# x-IMU3-SA-IMU.net
KiCad netlist of a schematic drawn in Altium Designer
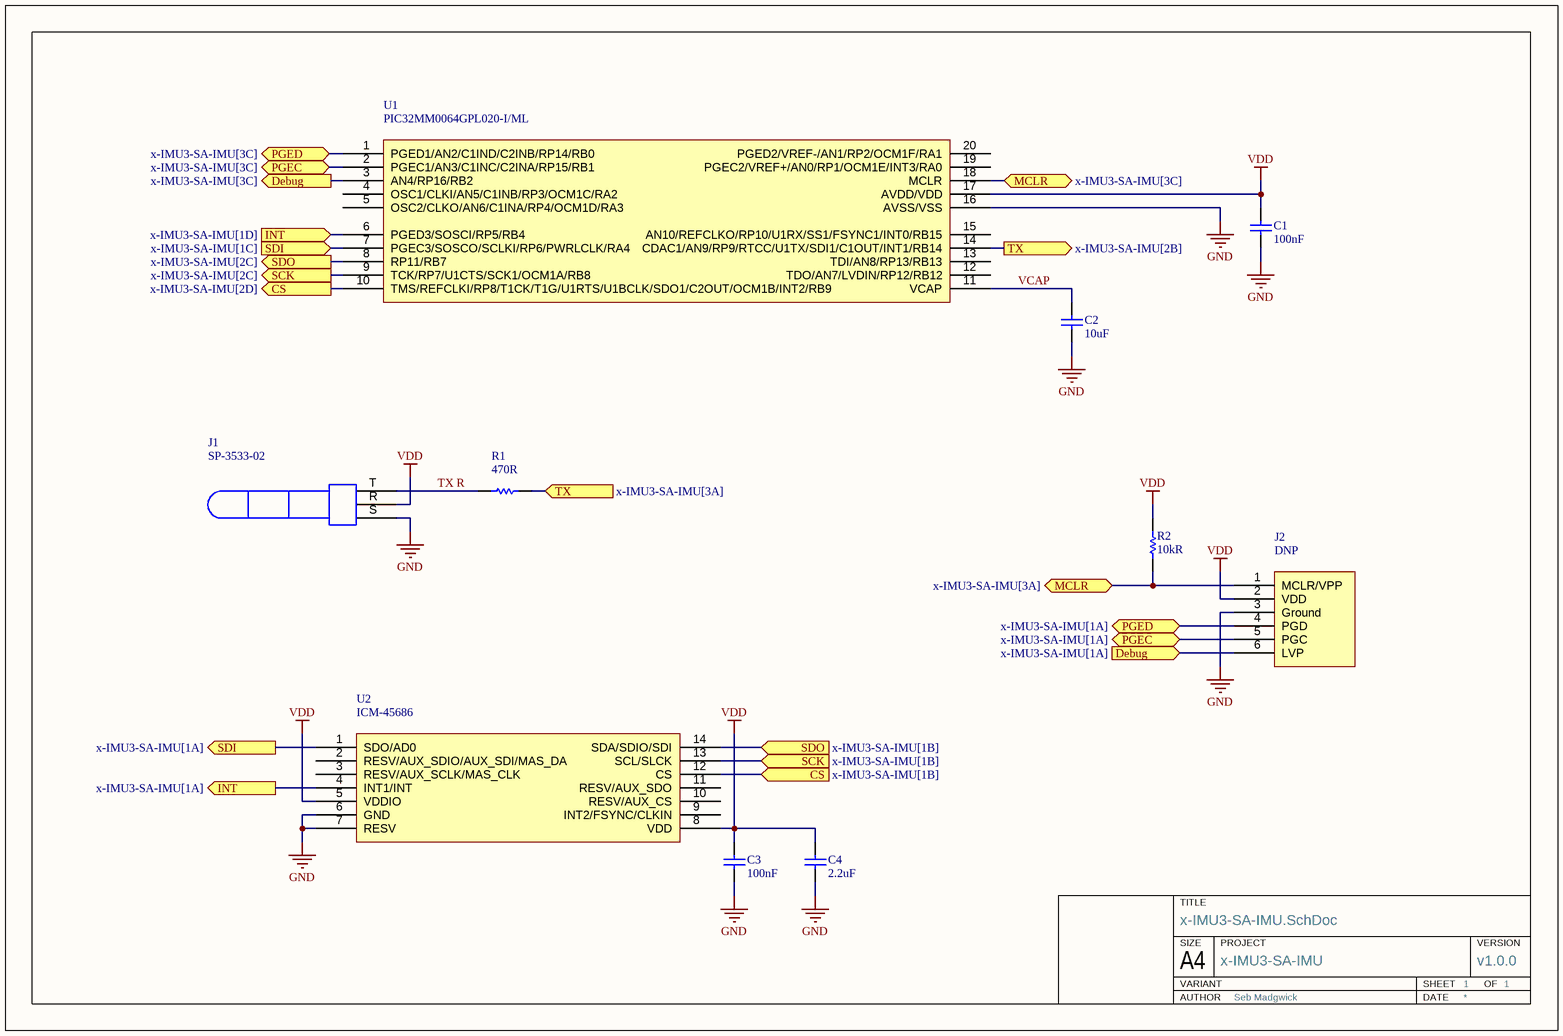
[diagram p0: x-IMU3-SA-IMU.SchDoc]

(export (version "E")
  (design (tool "Eeschema 10.0.6"))
  (components
    (comp (ref "C1") (value "100nF") (footprint "Capacitor 0402") (libsource (lib "x-io") (part "Capacitor")))
    (comp (ref "C2") (value "10uF") (footprint "Capacitor 0402") (libsource (lib "x-io") (part "Capacitor")))
    (comp (ref "C3") (value "100nF") (footprint "Capacitor 0402") (libsource (lib "x-io") (part "Capacitor")))
    (comp (ref "C4") (value "2.2uF") (footprint "Capacitor 0402") (libsource (lib "x-io") (part "Capacitor")))
    (comp (ref "J1")
      (value "SP-3533-02")
      (footprint "SP-3533-02")
      (libsource (lib "x-io") (part "SP-3533-02"))
    )
    (comp (ref "J2")
      (value "DNP")
      (footprint "Tag Connect No Legs")
      (libsource (lib "x-io") (part "MPLAB ICSP"))
    )
    (comp (ref "R1") (value "470R") (footprint "Resistor 0402") (libsource (lib "x-io") (part "Resistor")))
    (comp (ref "R2") (value "10kR") (footprint "Resistor 0402") (libsource (lib "x-io") (part "Resistor")))
    (comp (ref "U1")
      (value "PIC32MM0064GPL020-I/ML")
      (footprint "QFN-20")
      (libsource (lib "x-io") (part "PIC32MM0064GPL020-I/ML"))
    )
    (comp (ref "U2") (value "ICM-45686") (footprint "ICM-45686") (libsource (lib "x-io") (part "ICM-45686")))
  )
  (nets
    (net (code "1") (name "/CS") (class "Default")
      (node (ref "U1") (pin "10") (pinfunction "TMS/REFCLKI/RP8/T1CK/T1G/U1RTS/U1BCLK/SDO1/C2OUT/OCM1B/INT2/RB9_10") (pintype "passive"))
      (node (ref "U2") (pin "12") (pinfunction "CS_12") (pintype "passive"))
    )
    (net (code "2") (name "/Debug") (class "Default")
      (node (ref "J2") (pin "6") (pinfunction "LVP_6") (pintype "passive"))
      (node (ref "U1") (pin "3") (pinfunction "AN4/RP16/RB2_3") (pintype "passive"))
    )
    (net (code "3") (name "/INT") (class "Default")
      (node (ref "U1") (pin "6") (pinfunction "PGED3/SOSCI/RP5/RB4_6") (pintype "passive"))
      (node (ref "U2") (pin "4") (pinfunction "INT1/INT_4") (pintype "passive"))
    )
    (net (code "4") (name "/MCLR") (class "Default")
      (node (ref "J2") (pin "1") (pinfunction "MCLR/VPP_1") (pintype "passive"))
      (node (ref "R2") (pin "1") (pinfunction "1_1") (pintype "passive"))
      (node (ref "U1") (pin "18") (pinfunction "MCLR_18") (pintype "passive"))
    )
    (net (code "5") (name "/PGEC") (class "Default")
      (node (ref "J2") (pin "5") (pinfunction "PGC_5") (pintype "passive"))
      (node (ref "U1") (pin "2") (pinfunction "PGEC1/AN3/C1INC/C2INA/RP15/RB1_2") (pintype "passive"))
    )
    (net (code "6") (name "/PGED") (class "Default")
      (node (ref "J2") (pin "4") (pinfunction "PGD_4") (pintype "passive"))
      (node (ref "U1") (pin "1") (pinfunction "PGED1/AN2/C1IND/C2INB/RP14/RB0_1") (pintype "passive"))
    )
    (net (code "7") (name "/SCK") (class "Default")
      (node (ref "U1") (pin "9") (pinfunction "TCK/RP7/U1CTS/SCK1/OCM1A/RB8_9") (pintype "passive"))
      (node (ref "U2") (pin "13") (pinfunction "SCL/SLCK_13") (pintype "passive"))
    )
    (net (code "8") (name "/SDI") (class "Default")
      (node (ref "U1") (pin "7") (pinfunction "PGEC3/SOSCO/SCLKI/RP6/PWRLCLK/RA4_7") (pintype "passive"))
      (node (ref "U2") (pin "1") (pinfunction "SDO/AD0_1") (pintype "passive"))
    )
    (net (code "9") (name "/SDO") (class "Default")
      (node (ref "U1") (pin "8") (pinfunction "RP11/RB7_8") (pintype "passive"))
      (node (ref "U2") (pin "14") (pinfunction "SDA/SDIO/SDI_14") (pintype "passive"))
    )
    (net (code "10") (name "/TX") (class "Default")
      (node (ref "R1") (pin "2") (pinfunction "2_2") (pintype "passive"))
      (node (ref "U1") (pin "14") (pinfunction "CDAC1/AN9/RP9/RTCC/U1TX/SDI1/C1OUT/INT1/RB14_14") (pintype "passive"))
    )
    (net (code "11") (name "/TX R") (class "Default")
      (node (ref "J1") (pin "T") (pinfunction "T_T") (pintype "passive"))
      (node (ref "R1") (pin "1") (pinfunction "1_1") (pintype "passive"))
    )
    (net (code "12") (name "/VCAP") (class "Default")
      (node (ref "C2") (pin "2") (pinfunction "2_2") (pintype "passive"))
      (node (ref "U1") (pin "11") (pinfunction "VCAP_11") (pintype "passive"))
    )
    (net (code "13") (name "GND") (class "Default")
      (node (ref "C1") (pin "1") (pinfunction "1_1") (pintype "passive"))
      (node (ref "C2") (pin "1") (pinfunction "1_1") (pintype "passive"))
      (node (ref "C3") (pin "1") (pinfunction "1_1") (pintype "passive"))
      (node (ref "C4") (pin "1") (pinfunction "1_1") (pintype "passive"))
      (node (ref "J1") (pin "S") (pinfunction "S_S") (pintype "passive"))
      (node (ref "J2") (pin "3") (pinfunction "Ground_3") (pintype "passive"))
      (node (ref "U1") (pin "16") (pinfunction "AVSS/VSS_16") (pintype "passive"))
      (node (ref "U2") (pin "6") (pinfunction "GND_6") (pintype "passive"))
      (node (ref "U2") (pin "7") (pinfunction "RESV_7") (pintype "passive"))
    )
    (net (code "14") (name "VDD") (class "Default")
      (node (ref "C1") (pin "2") (pinfunction "2_2") (pintype "passive"))
      (node (ref "C3") (pin "2") (pinfunction "2_2") (pintype "passive"))
      (node (ref "C4") (pin "2") (pinfunction "2_2") (pintype "passive"))
      (node (ref "J1") (pin "R") (pinfunction "R_R") (pintype "passive"))
      (node (ref "J2") (pin "2") (pinfunction "VDD_2") (pintype "passive"))
      (node (ref "R2") (pin "2") (pinfunction "2_2") (pintype "passive"))
      (node (ref "U1") (pin "17") (pinfunction "AVDD/VDD_17") (pintype "passive"))
      (node (ref "U2") (pin "5") (pinfunction "VDDIO_5") (pintype "passive"))
      (node (ref "U2") (pin "8") (pinfunction "VDD_8") (pintype "passive"))
    )
    (net (code "15") (name "unconnected-(U1-AN10{slash}REFCLKO{slash}RP10{slash}U1RX{slash}SS1{slash}FSYNC1{slash}INT0{slash}RB15-Pad15)") (class "Default")
      (node (ref "U1") (pin "15") (pinfunction "AN10/REFCLKO/RP10/U1RX/SS1/FSYNC1/INT0/RB15_15") (pintype "passive"))
    )
    (net (code "16") (name "unconnected-(U1-OSC1{slash}CLKI{slash}AN5{slash}C1INB{slash}RP3{slash}OCM1C{slash}RA2-Pad4)") (class "Default")
      (node (ref "U1") (pin "4") (pinfunction "OSC1/CLKI/AN5/C1INB/RP3/OCM1C/RA2_4") (pintype "passive"))
    )
    (net (code "17") (name "unconnected-(U1-OSC2{slash}CLKO{slash}AN6{slash}C1INA{slash}RP4{slash}OCM1D{slash}RA3-Pad5)") (class "Default")
      (node (ref "U1") (pin "5") (pinfunction "OSC2/CLKO/AN6/C1INA/RP4/OCM1D/RA3_5") (pintype "passive"))
    )
    (net (code "18") (name "unconnected-(U1-PGEC2{slash}VREF+{slash}AN0{slash}RP1{slash}OCM1E{slash}INT3{slash}RA0-Pad19)") (class "Default")
      (node (ref "U1") (pin "19") (pinfunction "PGEC2/VREF+/AN0/RP1/OCM1E/INT3/RA0_19") (pintype "passive"))
    )
    (net (code "19") (name "unconnected-(U1-PGED2{slash}VREF-{slash}AN1{slash}RP2{slash}OCM1F{slash}RA1-Pad20)") (class "Default")
      (node (ref "U1") (pin "20") (pinfunction "PGED2/VREF-/AN1/RP2/OCM1F/RA1_20") (pintype "passive"))
    )
    (net (code "20") (name "unconnected-(U1-TDI{slash}AN8{slash}RP13{slash}RB13-Pad13)") (class "Default")
      (node (ref "U1") (pin "13") (pinfunction "TDI/AN8/RP13/RB13_13") (pintype "passive"))
    )
    (net (code "21") (name "unconnected-(U1-TDO{slash}AN7{slash}LVDIN{slash}RP12{slash}RB12-Pad12)") (class "Default")
      (node (ref "U1") (pin "12") (pinfunction "TDO/AN7/LVDIN/RP12/RB12_12") (pintype "passive"))
    )
    (net (code "22") (name "unconnected-(U2-INT2{slash}FSYNC{slash}CLKIN-Pad9)") (class "Default")
      (node (ref "U2") (pin "9") (pinfunction "INT2/FSYNC/CLKIN_9") (pintype "passive"))
    )
    (net (code "23") (name "unconnected-(U2-RESV{slash}AUX_CS-Pad10)") (class "Default")
      (node (ref "U2") (pin "10") (pinfunction "RESV/AUX_CS_10") (pintype "passive"))
    )
    (net (code "24") (name "unconnected-(U2-RESV{slash}AUX_SCLK{slash}MAS_CLK-Pad3)") (class "Default")
      (node (ref "U2") (pin "3") (pinfunction "RESV/AUX_SCLK/MAS_CLK_3") (pintype "passive"))
    )
    (net (code "25") (name "unconnected-(U2-RESV{slash}AUX_SDIO{slash}AUX_SDI{slash}MAS_DA-Pad2)") (class "Default")
      (node (ref "U2") (pin "2") (pinfunction "RESV/AUX_SDIO/AUX_SDI/MAS_DA_2") (pintype "passive"))
    )
    (net (code "26") (name "unconnected-(U2-RESV{slash}AUX_SDO-Pad11)") (class "Default")
      (node (ref "U2") (pin "11") (pinfunction "RESV/AUX_SDO_11") (pintype "passive"))
    )
  )
)
